# exp_xml.net
KiCad netlist of a schematic drawn in EAGLE
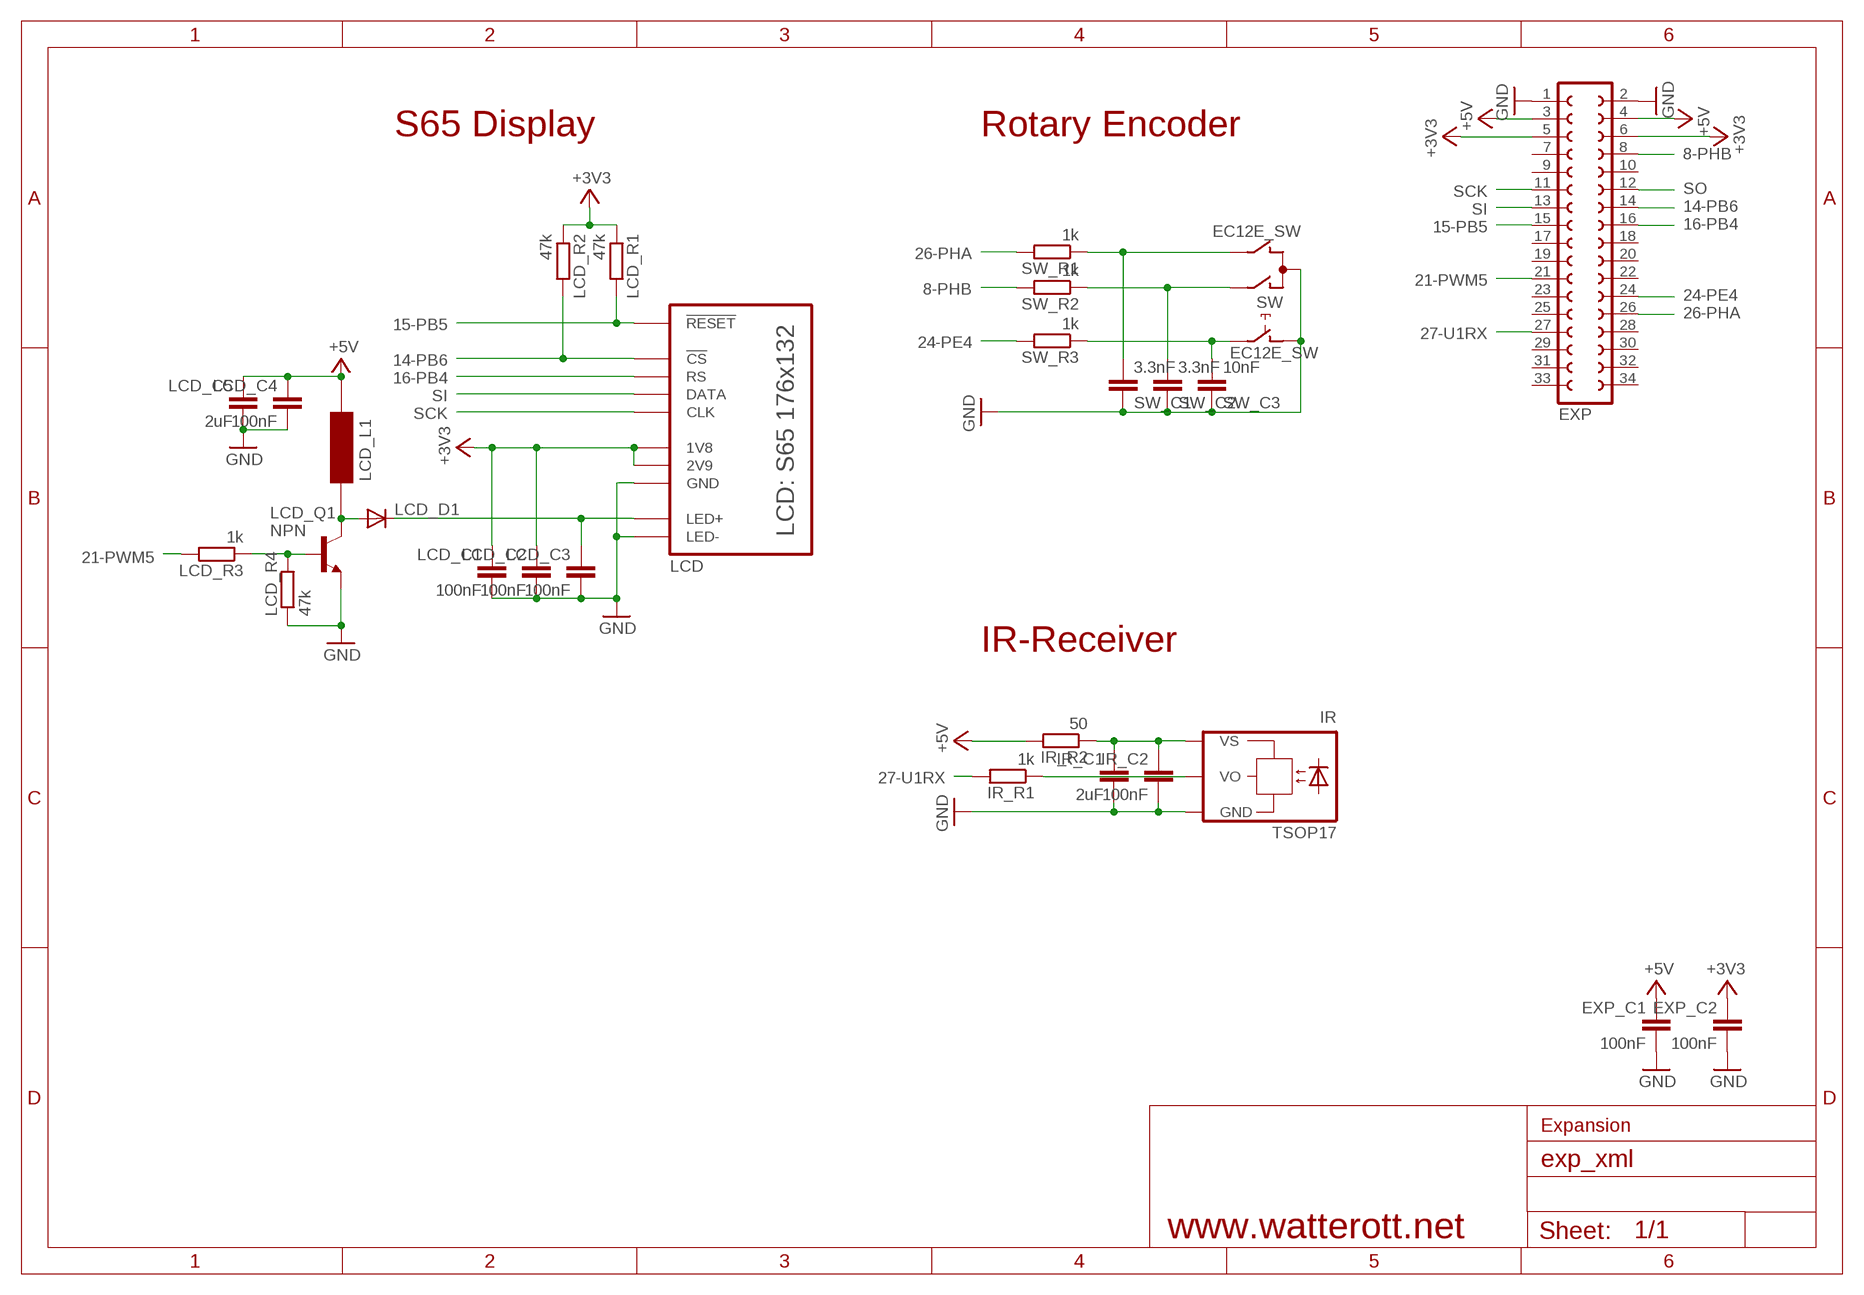
[diagram p0: schematic, sheet 1]

(export (version "E")
  (design (tool "Eeschema 10.0.6"))
  (components
    (comp (ref "EXP")
      (value "FE17-2SMD")
      (footprint "eagle-import:FE17-2_SMD")
      (libsource (lib "eagle-import") (part "FE17-2SMD"))
    )
    (comp (ref "EXP_C1")
      (value "100nF")
      (footprint "eagle-import:C0603")
      (libsource (lib "eagle-import") (part "C-EUC0603"))
    )
    (comp (ref "EXP_C2")
      (value "100nF")
      (footprint "eagle-import:C0603")
      (libsource (lib "eagle-import") (part "C-EUC0603"))
    )
    (comp (ref "IR")
      (value "TSOP17")
      (footprint "eagle-import:TSOP17")
      (libsource (lib "eagle-import") (part "TSOP17"))
    )
    (comp (ref "IR_C1")
      (value "2uF")
      (footprint "eagle-import:C0603")
      (libsource (lib "eagle-import") (part "C-EUC0603"))
    )
    (comp (ref "IR_C2")
      (value "100nF")
      (footprint "eagle-import:C0603")
      (libsource (lib "eagle-import") (part "C-EUC0603"))
    )
    (comp (ref "IR_R1")
      (value "1k")
      (footprint "eagle-import:R0603")
      (libsource (lib "eagle-import") (part "R-EU_R0603"))
    )
    (comp (ref "IR_R2")
      (value "50")
      (footprint "eagle-import:R0603")
      (libsource (lib "eagle-import") (part "R-EU_R0603"))
    )
    (comp (ref "LCD")
      (value "S65")
      (footprint "eagle-import:S65")
      (libsource (lib "eagle-import") (part "S65"))
    )
    (comp (ref "LCD_C1")
      (value "100nF")
      (footprint "eagle-import:C0603")
      (libsource (lib "eagle-import") (part "C-EUC0603"))
    )
    (comp (ref "LCD_C2")
      (value "100nF")
      (footprint "eagle-import:C0603")
      (libsource (lib "eagle-import") (part "C-EUC0603"))
    )
    (comp (ref "LCD_C3")
      (value "100nF")
      (footprint "eagle-import:C0603")
      (libsource (lib "eagle-import") (part "C-EUC0603"))
    )
    (comp (ref "LCD_C4")
      (value "100nF")
      (footprint "eagle-import:C0805")
      (libsource (lib "eagle-import") (part "C-EUC0805"))
    )
    (comp (ref "LCD_C5")
      (value "2uF")
      (footprint "eagle-import:C0805")
      (libsource (lib "eagle-import") (part "C-EUC0805"))
    )
    (comp (ref "LCD_D1")
      (value "Schottky")
      (footprint "eagle-import:DO214AA")
      (libsource (lib "eagle-import") (part "DIODE-DO214AA"))
    )
    (comp (ref "LCD_L1")
      (value "2mH")
      (footprint "eagle-import:WE-PD3-S")
      (libsource (lib "eagle-import") (part "WE-PD3-S"))
    )
    (comp (ref "LCD_Q1")
      (value "NPN")
      (footprint "eagle-import:SOT23")
      (libsource (lib "eagle-import") (part "NPN"))
    )
    (comp (ref "LCD_R1")
      (value "47k")
      (footprint "eagle-import:R0603")
      (libsource (lib "eagle-import") (part "R-EU_R0603"))
    )
    (comp (ref "LCD_R2")
      (value "47k")
      (footprint "eagle-import:R0603")
      (libsource (lib "eagle-import") (part "R-EU_R0603"))
    )
    (comp (ref "LCD_R3")
      (value "1k")
      (footprint "eagle-import:R0603")
      (libsource (lib "eagle-import") (part "R-EU_R0603"))
    )
    (comp (ref "LCD_R4")
      (value "47k")
      (footprint "eagle-import:R0603")
      (libsource (lib "eagle-import") (part "R-EU_R0603"))
    )
    (comp (ref "SW")
      (value "EC12E_SW")
      (footprint "eagle-import:ALPS_EC12E_SW")
      (libsource (lib "eagle-import") (part "EC12E_SW"))
    )
    (comp (ref "SW_C1")
      (value "3.3nF")
      (footprint "eagle-import:C0603")
      (libsource (lib "eagle-import") (part "C-EUC0603"))
    )
    (comp (ref "SW_C2")
      (value "3.3nF")
      (footprint "eagle-import:C0603")
      (libsource (lib "eagle-import") (part "C-EUC0603"))
    )
    (comp (ref "SW_C3")
      (value "10nF")
      (footprint "eagle-import:C0603")
      (libsource (lib "eagle-import") (part "C-EUC0603"))
    )
    (comp (ref "SW_R1")
      (value "1k")
      (footprint "eagle-import:R0603")
      (libsource (lib "eagle-import") (part "R-EU_R0603"))
    )
    (comp (ref "SW_R2")
      (value "1k")
      (footprint "eagle-import:R0603")
      (libsource (lib "eagle-import") (part "R-EU_R0603"))
    )
    (comp (ref "SW_R3")
      (value "1k")
      (footprint "eagle-import:R0603")
      (libsource (lib "eagle-import") (part "R-EU_R0603"))
    )
  )
  (nets
    (net (code "1") (name "+3V3") (class "Default")
      (node (ref "EXP") (pin "5") (pinfunction "5_5") (pintype "passive"))
      (node (ref "EXP") (pin "6") (pinfunction "6_6") (pintype "passive"))
      (node (ref "EXP_C2") (pin "1") (pinfunction "1_1") (pintype "passive"))
      (node (ref "LCD") (pin "1V8") (pinfunction "1V8_1V8") (pintype "power_in"))
      (node (ref "LCD") (pin "2V9") (pinfunction "2V9_2V9") (pintype "power_in"))
      (node (ref "LCD_C1") (pin "1") (pinfunction "1_1") (pintype "passive"))
      (node (ref "LCD_C2") (pin "1") (pinfunction "1_1") (pintype "passive"))
      (node (ref "LCD_R1") (pin "1") (pinfunction "1_1") (pintype "passive"))
      (node (ref "LCD_R2") (pin "1") (pinfunction "1_1") (pintype "passive"))
    )
    (net (code "2") (name "+5V") (class "Default")
      (node (ref "EXP") (pin "3") (pinfunction "3_3") (pintype "passive"))
      (node (ref "EXP") (pin "4") (pinfunction "4_4") (pintype "passive"))
      (node (ref "EXP_C1") (pin "1") (pinfunction "1_1") (pintype "passive"))
      (node (ref "IR_R2") (pin "2") (pinfunction "2_2") (pintype "passive"))
      (node (ref "LCD_C4") (pin "1") (pinfunction "1_1") (pintype "passive"))
      (node (ref "LCD_C5") (pin "1") (pinfunction "1_1") (pintype "passive"))
      (node (ref "LCD_L1") (pin "P$2") (pinfunction "P$2_P$2") (pintype "bidirectional"))
    )
    (net (code "3") (name "/8-PHB") (class "Default")
      (node (ref "EXP") (pin "8") (pinfunction "8_8") (pintype "passive"))
      (node (ref "SW_R2") (pin "2") (pinfunction "2_2") (pintype "passive"))
    )
    (net (code "4") (name "/14-PB6") (class "Default")
      (node (ref "EXP") (pin "14") (pinfunction "14_14") (pintype "passive"))
      (node (ref "LCD") (pin "CS") (pinfunction "~{CS}_CS") (pintype "bidirectional"))
      (node (ref "LCD_R2") (pin "2") (pinfunction "2_2") (pintype "passive"))
    )
    (net (code "5") (name "/15-PB5") (class "Default")
      (node (ref "EXP") (pin "15") (pinfunction "15_15") (pintype "passive"))
      (node (ref "LCD") (pin "RESET") (pinfunction "~{RESET}_RESET") (pintype "bidirectional"))
      (node (ref "LCD_R1") (pin "2") (pinfunction "2_2") (pintype "passive"))
    )
    (net (code "6") (name "/16-PB4") (class "Default")
      (node (ref "EXP") (pin "16") (pinfunction "16_16") (pintype "passive"))
      (node (ref "LCD") (pin "RS") (pinfunction "RS_RS") (pintype "bidirectional"))
    )
    (net (code "7") (name "/21-PWM5") (class "Default")
      (node (ref "EXP") (pin "21") (pinfunction "21_21") (pintype "passive"))
      (node (ref "LCD_R3") (pin "2") (pinfunction "2_2") (pintype "passive"))
    )
    (net (code "8") (name "/24-PE4") (class "Default")
      (node (ref "EXP") (pin "24") (pinfunction "24_24") (pintype "passive"))
      (node (ref "SW_R3") (pin "2") (pinfunction "2_2") (pintype "passive"))
    )
    (net (code "9") (name "/26-PHA") (class "Default")
      (node (ref "EXP") (pin "26") (pinfunction "26_26") (pintype "passive"))
      (node (ref "SW_R1") (pin "2") (pinfunction "2_2") (pintype "passive"))
    )
    (net (code "10") (name "/27-U1RX") (class "Default")
      (node (ref "EXP") (pin "27") (pinfunction "27_27") (pintype "passive"))
      (node (ref "IR_R1") (pin "2") (pinfunction "2_2") (pintype "passive"))
    )
    (net (code "11") (name "/SCK") (class "Default")
      (node (ref "EXP") (pin "11") (pinfunction "11_11") (pintype "passive"))
      (node (ref "LCD") (pin "CLK") (pinfunction "CLK_CLK") (pintype "bidirectional"))
    )
    (net (code "12") (name "/SI") (class "Default")
      (node (ref "EXP") (pin "13") (pinfunction "13_13") (pintype "passive"))
      (node (ref "LCD") (pin "DATA") (pinfunction "DATA_DATA") (pintype "bidirectional"))
    )
    (net (code "13") (name "/SO") (class "Default")
      (node (ref "EXP") (pin "12") (pinfunction "12_12") (pintype "passive"))
    )
    (net (code "14") (name "GND") (class "Default")
      (node (ref "EXP") (pin "1") (pinfunction "1_1") (pintype "passive"))
      (node (ref "EXP") (pin "2") (pinfunction "2_2") (pintype "passive"))
      (node (ref "EXP_C1") (pin "2") (pinfunction "2_2") (pintype "passive"))
      (node (ref "EXP_C2") (pin "2") (pinfunction "2_2") (pintype "passive"))
      (node (ref "IR") (pin "GND") (pinfunction "GND_GND") (pintype "power_in"))
      (node (ref "IR_C1") (pin "2") (pinfunction "2_2") (pintype "passive"))
      (node (ref "IR_C2") (pin "2") (pinfunction "2_2") (pintype "passive"))
      (node (ref "LCD") (pin "GND") (pinfunction "GND_GND") (pintype "power_in"))
      (node (ref "LCD") (pin "LED-") (pinfunction "LED-_LED-") (pintype "power_in"))
      (node (ref "LCD_C1") (pin "2") (pinfunction "2_2") (pintype "passive"))
      (node (ref "LCD_C2") (pin "2") (pinfunction "2_2") (pintype "passive"))
      (node (ref "LCD_C3") (pin "2") (pinfunction "2_2") (pintype "passive"))
      (node (ref "LCD_C4") (pin "2") (pinfunction "2_2") (pintype "passive"))
      (node (ref "LCD_C5") (pin "2") (pinfunction "2_2") (pintype "passive"))
      (node (ref "LCD_Q1") (pin "2") (pinfunction "E_2") (pintype "passive"))
      (node (ref "LCD_R4") (pin "1") (pinfunction "1_1") (pintype "passive"))
      (node (ref "SW") (pin "C") (pinfunction "C_C") (pintype "passive"))
      (node (ref "SW") (pin "D") (pinfunction "1_D") (pintype "passive"))
      (node (ref "SW_C1") (pin "1") (pinfunction "1_1") (pintype "passive"))
      (node (ref "SW_C2") (pin "1") (pinfunction "1_1") (pintype "passive"))
      (node (ref "SW_C3") (pin "1") (pinfunction "1_1") (pintype "passive"))
    )
    (net (code "15") (name "Net-(IR-PadVO)") (class "Default")
      (node (ref "IR") (pin "VO") (pinfunction "VO_VO") (pintype "open_collector"))
      (node (ref "IR_R1") (pin "1") (pinfunction "1_1") (pintype "passive"))
    )
    (net (code "16") (name "Net-(IR-PadVS)") (class "Default")
      (node (ref "IR") (pin "VS") (pinfunction "VS_VS") (pintype "power_in"))
      (node (ref "IR_C1") (pin "1") (pinfunction "1_1") (pintype "passive"))
      (node (ref "IR_C2") (pin "1") (pinfunction "1_1") (pintype "passive"))
      (node (ref "IR_R2") (pin "1") (pinfunction "1_1") (pintype "passive"))
    )
    (net (code "17") (name "Net-(LCD-PadLED+)") (class "Default")
      (node (ref "LCD") (pin "LED+") (pinfunction "LED+_LED+") (pintype "power_in"))
      (node (ref "LCD_C3") (pin "1") (pinfunction "1_1") (pintype "passive"))
      (node (ref "LCD_D1") (pin "C") (pinfunction "C_C") (pintype "passive"))
    )
    (net (code "18") (name "Net-(LCD_Q1-B)") (class "Default")
      (node (ref "LCD_Q1") (pin "1") (pinfunction "B_1") (pintype "passive"))
      (node (ref "LCD_R3") (pin "1") (pinfunction "1_1") (pintype "passive"))
      (node (ref "LCD_R4") (pin "2") (pinfunction "2_2") (pintype "passive"))
    )
    (net (code "19") (name "Net-(LCD_Q1-C)") (class "Default")
      (node (ref "LCD_D1") (pin "A") (pinfunction "A_A") (pintype "passive"))
      (node (ref "LCD_L1") (pin "P$1") (pinfunction "P$1_P$1") (pintype "bidirectional"))
      (node (ref "LCD_Q1") (pin "3") (pinfunction "C_3") (pintype "passive"))
    )
    (net (code "20") (name "Net-(SW-PadA)") (class "Default")
      (node (ref "SW") (pin "A") (pinfunction "A_A") (pintype "passive"))
      (node (ref "SW_C2") (pin "2") (pinfunction "2_2") (pintype "passive"))
      (node (ref "SW_R2") (pin "1") (pinfunction "1_1") (pintype "passive"))
    )
    (net (code "21") (name "Net-(SW-PadB)") (class "Default")
      (node (ref "SW") (pin "B") (pinfunction "B_B") (pintype "passive"))
      (node (ref "SW_C1") (pin "2") (pinfunction "2_2") (pintype "passive"))
      (node (ref "SW_R1") (pin "1") (pinfunction "1_1") (pintype "passive"))
    )
    (net (code "22") (name "Net-(SWB-2)") (class "Default")
      (node (ref "SW") (pin "E") (pinfunction "2_E") (pintype "passive"))
      (node (ref "SW_C3") (pin "2") (pinfunction "2_2") (pintype "passive"))
      (node (ref "SW_R3") (pin "1") (pinfunction "1_1") (pintype "passive"))
    )
    (net (code "23") (name "unconnected-(EXP-Pad7)") (class "Default")
      (node (ref "EXP") (pin "7") (pinfunction "7_7") (pintype "passive"))
    )
    (net (code "24") (name "unconnected-(EXP-Pad9)") (class "Default")
      (node (ref "EXP") (pin "9") (pinfunction "9_9") (pintype "passive"))
    )
    (net (code "25") (name "unconnected-(EXP-Pad10)") (class "Default")
      (node (ref "EXP") (pin "10") (pinfunction "10_10") (pintype "passive"))
    )
    (net (code "26") (name "unconnected-(EXP-Pad17)") (class "Default")
      (node (ref "EXP") (pin "17") (pinfunction "17_17") (pintype "passive"))
    )
    (net (code "27") (name "unconnected-(EXP-Pad18)") (class "Default")
      (node (ref "EXP") (pin "18") (pinfunction "18_18") (pintype "passive"))
    )
    (net (code "28") (name "unconnected-(EXP-Pad19)") (class "Default")
      (node (ref "EXP") (pin "19") (pinfunction "19_19") (pintype "passive"))
    )
    (net (code "29") (name "unconnected-(EXP-Pad20)") (class "Default")
      (node (ref "EXP") (pin "20") (pinfunction "20_20") (pintype "passive"))
    )
    (net (code "30") (name "unconnected-(EXP-Pad22)") (class "Default")
      (node (ref "EXP") (pin "22") (pinfunction "22_22") (pintype "passive"))
    )
    (net (code "31") (name "unconnected-(EXP-Pad23)") (class "Default")
      (node (ref "EXP") (pin "23") (pinfunction "23_23") (pintype "passive"))
    )
    (net (code "32") (name "unconnected-(EXP-Pad25)") (class "Default")
      (node (ref "EXP") (pin "25") (pinfunction "25_25") (pintype "passive"))
    )
    (net (code "33") (name "unconnected-(EXP-Pad28)") (class "Default")
      (node (ref "EXP") (pin "28") (pinfunction "28_28") (pintype "passive"))
    )
    (net (code "34") (name "unconnected-(EXP-Pad29)") (class "Default")
      (node (ref "EXP") (pin "29") (pinfunction "29_29") (pintype "passive"))
    )
    (net (code "35") (name "unconnected-(EXP-Pad30)") (class "Default")
      (node (ref "EXP") (pin "30") (pinfunction "30_30") (pintype "passive"))
    )
    (net (code "36") (name "unconnected-(EXP-Pad31)") (class "Default")
      (node (ref "EXP") (pin "31") (pinfunction "31_31") (pintype "passive"))
    )
    (net (code "37") (name "unconnected-(EXP-Pad32)") (class "Default")
      (node (ref "EXP") (pin "32") (pinfunction "32_32") (pintype "passive"))
    )
    (net (code "38") (name "unconnected-(EXP-Pad33)") (class "Default")
      (node (ref "EXP") (pin "33") (pinfunction "33_33") (pintype "passive"))
    )
    (net (code "39") (name "unconnected-(EXP-Pad34)") (class "Default")
      (node (ref "EXP") (pin "34") (pinfunction "34_34") (pintype "passive"))
    )
  )
)
